# MrRoboto.net
KiCad netlist of a schematic drawn in EAGLE
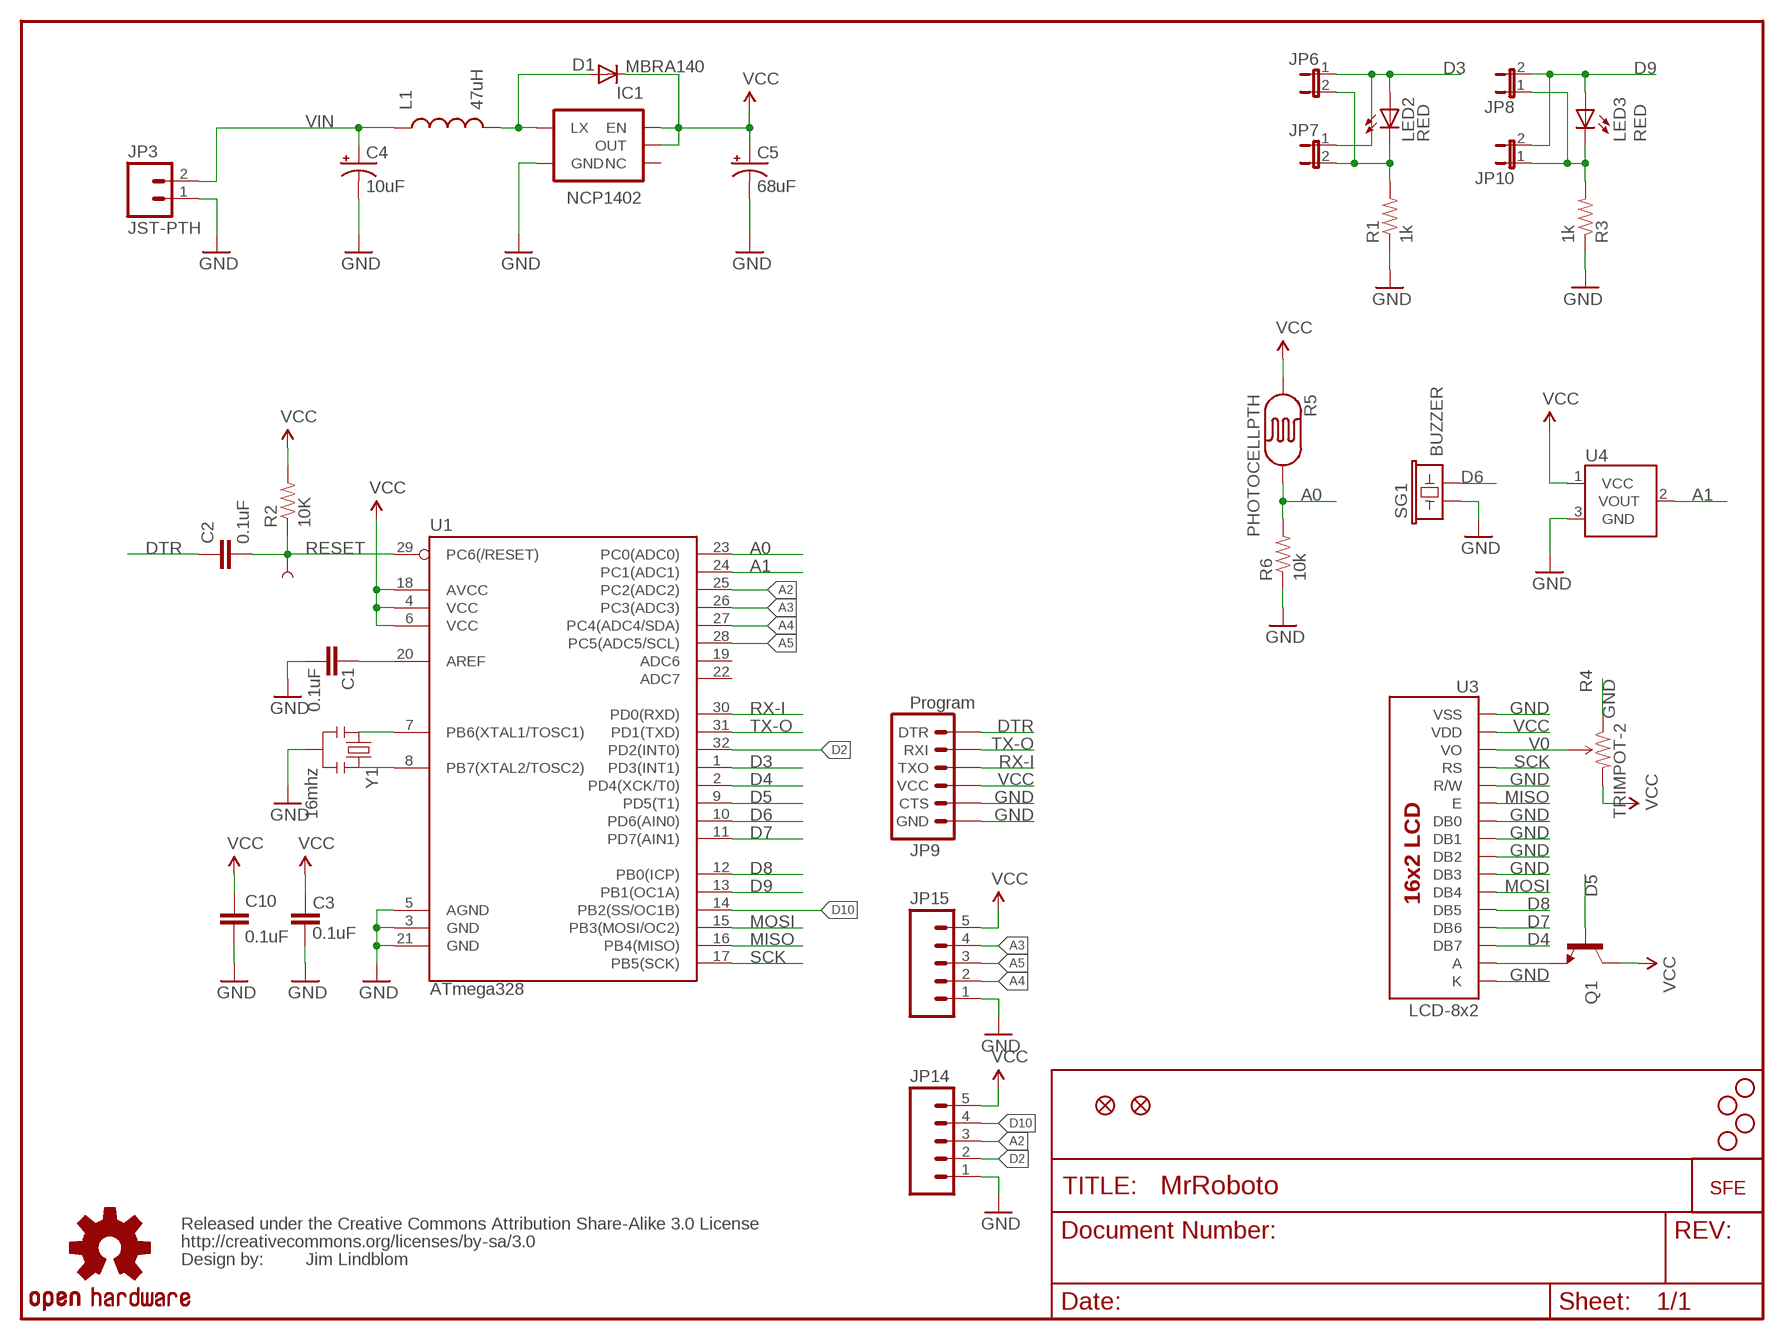
[diagram p0: schematic, sheet 1]

(export (version "E")
  (design (tool "Eeschema 10.0.6"))
  (components
    (comp (ref "C1")
      (value "0.1uF")
      (footprint "eagle-import:0402-CAP")
      (libsource (lib "eagle-import") (part "CAP0402-CAP"))
    )
    (comp (ref "C2")
      (value "0.1uF")
      (footprint "eagle-import:0402-CAP")
      (libsource (lib "eagle-import") (part "CAP0402-CAP"))
    )
    (comp (ref "C3")
      (value "0.1uF")
      (footprint "eagle-import:0402-CAP")
      (libsource (lib "eagle-import") (part "CAP0402-CAP"))
    )
    (comp (ref "C4")
      (value "10uF")
      (footprint "eagle-import:EIA3216")
      (libsource (lib "eagle-import") (part "CAP_POL1206"))
    )
    (comp (ref "C5")
      (value "68uF")
      (footprint "eagle-import:EIA3528")
      (libsource (lib "eagle-import") (part "CAP_POL3528"))
    )
    (comp (ref "C10")
      (value "0.1uF")
      (footprint "eagle-import:0402-CAP")
      (libsource (lib "eagle-import") (part "CAP0402-CAP"))
    )
    (comp (ref "D1")
      (value "MBRA140")
      (footprint "eagle-import:SMA-DIODE")
      (libsource (lib "eagle-import") (part "DIODESMA"))
    )
    (comp (ref "IC1")
      (value "NCP1402")
      (footprint "eagle-import:SOT23-5")
      (libsource (lib "eagle-import") (part "V_REG_NCP1400SOT23-5"))
    )
    (comp (ref "JP1")
      (value "Long, Plastic")
      (footprint "eagle-import:STAND-OFF")
      (libsource (lib "eagle-import") (part "STAND-OFF"))
    )
    (comp (ref "JP2")
      (value "Long, Plastic")
      (footprint "eagle-import:STAND-OFF")
      (libsource (lib "eagle-import") (part "STAND-OFF"))
    )
    (comp (ref "JP3")
      (value "JST-PTH")
      (footprint "eagle-import:JST-2-PTH-KIT")
      (libsource (lib "eagle-import") (part "M02JST-PTH-2-KIT"))
    )
    (comp (ref "JP4")
      (value "Long, Plastic")
      (footprint "eagle-import:STAND-OFF")
      (libsource (lib "eagle-import") (part "STAND-OFF"))
    )
    (comp (ref "JP5")
      (value "Long, Plastic")
      (footprint "eagle-import:STAND-OFF")
      (libsource (lib "eagle-import") (part "STAND-OFF"))
    )
    (comp (ref "JP6")
      (value "JUMPER-2SMD-NO-NS")
      (footprint "eagle-import:SJ_2S-NO-NS")
      (libsource (lib "eagle-import") (part "JUMPER-2SMD-NO-NS"))
    )
    (comp (ref "JP7")
      (value "JUMPER-2SMD-NO-NS")
      (footprint "eagle-import:SJ_2S-NO-NS")
      (libsource (lib "eagle-import") (part "JUMPER-2SMD-NO-NS"))
    )
    (comp (ref "JP8")
      (value "JUMPER-2SMD-NO-NS")
      (footprint "eagle-import:SJ_2S-NO-NS")
      (libsource (lib "eagle-import") (part "JUMPER-2SMD-NO-NS"))
    )
    (comp (ref "JP9")
      (value "Program")
      (footprint "eagle-import:1X06-KIT")
      (libsource (lib "eagle-import") (part "ARDUINO_SERIAL_PROGRAMPTH-KIT"))
    )
    (comp (ref "JP10")
      (value "JUMPER-2SMD-NO-NS")
      (footprint "eagle-import:SJ_2S-NO-NS")
      (libsource (lib "eagle-import") (part "JUMPER-2SMD-NO-NS"))
    )
    (comp (ref "JP11")
      (value "FIDUCIAL1X2.5")
      (footprint "eagle-import:FIDUCIAL-1X2.5")
      (libsource (lib "eagle-import") (part "FIDUCIAL1X2.5"))
    )
    (comp (ref "JP12")
      (value "FIDUCIAL1X2.5")
      (footprint "eagle-import:FIDUCIAL-1X2.5")
      (libsource (lib "eagle-import") (part "FIDUCIAL1X2.5"))
    )
    (comp (ref "JP14")
      (value "M05PTH")
      (footprint "eagle-import:1X05")
      (libsource (lib "eagle-import") (part "M05PTH"))
    )
    (comp (ref "JP15")
      (value "M05PTH")
      (footprint "eagle-import:1X05")
      (libsource (lib "eagle-import") (part "M05PTH"))
    )
    (comp (ref "L1")
      (value "47uH")
      (footprint "eagle-import:CR54")
      (libsource (lib "eagle-import") (part "INDUCTORCR54"))
    )
    (comp (ref "LED2")
      (value "RED")
      (footprint "eagle-import:LED5MM-KIT")
      (libsource (lib "eagle-import") (part "LED5MM-KIT"))
    )
    (comp (ref "LED3")
      (value "RED")
      (footprint "eagle-import:LED5MM-KIT")
      (libsource (lib "eagle-import") (part "LED5MM-KIT"))
    )
    (comp (ref "Q1")
      (value "TRANSISTOR_NPNSOT23")
      (footprint "eagle-import:SOT23")
      (libsource (lib "eagle-import") (part "TRANSISTOR_NPNSOT23"))
    )
    (comp (ref "R1")
      (value "1k")
      (footprint "eagle-import:AXIAL-0.3-KIT")
      (libsource (lib "eagle-import") (part "RESISTORKIT"))
    )
    (comp (ref "R2")
      (value "10K")
      (footprint "eagle-import:0402-RES")
      (libsource (lib "eagle-import") (part "RESISTOR0402-RES"))
    )
    (comp (ref "R3")
      (value "1k")
      (footprint "eagle-import:AXIAL-0.3-KIT")
      (libsource (lib "eagle-import") (part "RESISTORKIT"))
    )
    (comp (ref "R4")
      (value "TRIMPOT-2")
      (footprint "eagle-import:TRIMPOT_TC33")
      (libsource (lib "eagle-import") (part "TRIMPOT-2"))
    )
    (comp (ref "R5")
      (value "PHOTOCELLPTH")
      (footprint "eagle-import:PHOTOCELL-KIT")
      (libsource (lib "eagle-import") (part "PHOTOCELLPTH-KIT"))
    )
    (comp (ref "R6")
      (value "10k")
      (footprint "eagle-import:0402-RES")
      (libsource (lib "eagle-import") (part "RESISTOR0402-RES"))
    )
    (comp (ref "SG1")
      (value "BUZZER")
      (footprint "eagle-import:BUZZER-12MM-NS-KIT")
      (libsource (lib "eagle-import") (part "BUZZERPTH-NS-KIT"))
    )
    (comp (ref "TP1")
      (value "TP")
      (footprint "eagle-import:PAD.03X.05")
      (libsource (lib "eagle-import") (part "TEST-POINT3X5"))
    )
    (comp (ref "U$1")
      (value "CREATIVE_COMMONS")
      (footprint "eagle-import:CREATIVE_COMMONS")
      (libsource (lib "eagle-import") (part "CREATIVE_COMMONS"))
    )
    (comp (ref "U$2")
      (value "OSHW-LOGOM")
      (footprint "eagle-import:OSHW-LOGO-M")
      (libsource (lib "eagle-import") (part "OSHW-LOGOM"))
    )
    (comp (ref "U$3")
      (value "LOGO-SFENEW")
      (footprint "eagle-import:SFE-NEW-WEBLOGO")
      (libsource (lib "eagle-import") (part "LOGO-SFENEW"))
    )
    (comp (ref "U1")
      (value "ATmega328")
      (footprint "eagle-import:TQFP32-08")
      (libsource (lib "eagle-import") (part "ATMEGA168"))
    )
    (comp (ref "U3")
      (value "LCD-8x2")
      (footprint "eagle-import:LCD-8X2-KIT")
      (libsource (lib "eagle-import") (part "LCD-16X28X2-KIT"))
    )
    (comp (ref "U4")
      (value "TMP36TO-92-KIT")
      (footprint "eagle-import:TO-92-KIT")
      (libsource (lib "eagle-import") (part "TMP36TO-92-KIT"))
    )
    (comp (ref "Y1")
      (value "16mhz")
      (footprint "eagle-import:RESONATOR-SMD")
      (libsource (lib "eagle-import") (part "RESONATORSMD"))
    )
  )
  (nets
    (net (code "1") (name "/A0") (class "Default")
      (node (ref "R5") (pin "2") (pinfunction "P$2_2") (pintype "bidirectional"))
      (node (ref "R6") (pin "2") (pinfunction "2_2") (pintype "passive"))
      (node (ref "U1") (pin "23") (pinfunction "PC0(ADC0)_23") (pintype "bidirectional"))
    )
    (net (code "2") (name "/A1") (class "Default")
      (node (ref "U1") (pin "24") (pinfunction "PC1(ADC1)_24") (pintype "bidirectional"))
      (node (ref "U4") (pin "2") (pinfunction "VOUT_2") (pintype "bidirectional"))
    )
    (net (code "3") (name "/D3") (class "Default")
      (node (ref "JP6") (pin "1") (pinfunction "1_1") (pintype "passive"))
      (node (ref "JP7") (pin "1") (pinfunction "1_1") (pintype "passive"))
      (node (ref "LED2") (pin "A") (pinfunction "A_A") (pintype "passive"))
      (node (ref "U1") (pin "1") (pinfunction "PD3(INT1)_1") (pintype "bidirectional"))
    )
    (net (code "4") (name "/D4") (class "Default")
      (node (ref "U1") (pin "2") (pinfunction "PD4(XCK/T0)_2") (pintype "bidirectional"))
      (node (ref "U3") (pin "14") (pinfunction "DB7_14") (pintype "bidirectional"))
    )
    (net (code "5") (name "/D5") (class "Default")
      (node (ref "Q1") (pin "1") (pinfunction "B_1") (pintype "passive"))
      (node (ref "U1") (pin "9") (pinfunction "PD5(T1)_9") (pintype "bidirectional"))
    )
    (net (code "6") (name "/D6") (class "Default")
      (node (ref "SG1") (pin "-") (pinfunction "2_-") (pintype "passive"))
      (node (ref "U1") (pin "10") (pinfunction "PD6(AIN0)_10") (pintype "bidirectional"))
    )
    (net (code "7") (name "/D7") (class "Default")
      (node (ref "U1") (pin "11") (pinfunction "PD7(AIN1)_11") (pintype "bidirectional"))
      (node (ref "U3") (pin "13") (pinfunction "DB6_13") (pintype "bidirectional"))
    )
    (net (code "8") (name "/D8") (class "Default")
      (node (ref "U1") (pin "12") (pinfunction "PB0(ICP)_12") (pintype "bidirectional"))
      (node (ref "U3") (pin "12") (pinfunction "DB5_12") (pintype "bidirectional"))
    )
    (net (code "9") (name "/D9") (class "Default")
      (node (ref "JP10") (pin "2") (pinfunction "2_2") (pintype "passive"))
      (node (ref "JP8") (pin "2") (pinfunction "2_2") (pintype "passive"))
      (node (ref "LED3") (pin "A") (pinfunction "A_A") (pintype "passive"))
      (node (ref "U1") (pin "13") (pinfunction "PB1(OC1A)_13") (pintype "bidirectional"))
    )
    (net (code "10") (name "/DTR") (class "Default")
      (node (ref "C2") (pin "1") (pinfunction "1_1") (pintype "passive"))
      (node (ref "JP9") (pin "1") (pinfunction "DTR_1") (pintype "passive"))
    )
    (net (code "11") (name "/MISO") (class "Default")
      (node (ref "U1") (pin "16") (pinfunction "PB4(MISO)_16") (pintype "bidirectional"))
      (node (ref "U3") (pin "6") (pinfunction "E_6") (pintype "input"))
    )
    (net (code "12") (name "/MOSI") (class "Default")
      (node (ref "U1") (pin "15") (pinfunction "PB3(MOSI/OC2)_15") (pintype "bidirectional"))
      (node (ref "U3") (pin "11") (pinfunction "DB4_11") (pintype "bidirectional"))
    )
    (net (code "13") (name "/RESET") (class "Default")
      (node (ref "C2") (pin "2") (pinfunction "2_2") (pintype "passive"))
      (node (ref "R2") (pin "1") (pinfunction "1_1") (pintype "passive"))
      (node (ref "TP1") (pin "P$1") (pinfunction "1_P$1") (pintype "bidirectional"))
      (node (ref "U1") (pin "29") (pinfunction "PC6(/RESET)_29") (pintype "bidirectional"))
    )
    (net (code "14") (name "/RX-I") (class "Default")
      (node (ref "JP9") (pin "3") (pinfunction "TXO_3") (pintype "passive"))
      (node (ref "U1") (pin "30") (pinfunction "PD0(RXD)_30") (pintype "bidirectional"))
    )
    (net (code "15") (name "/SCK") (class "Default")
      (node (ref "U1") (pin "17") (pinfunction "PB5(SCK)_17") (pintype "bidirectional"))
      (node (ref "U3") (pin "4") (pinfunction "RS_4") (pintype "input"))
    )
    (net (code "16") (name "/TX-O") (class "Default")
      (node (ref "JP9") (pin "2") (pinfunction "RXI_2") (pintype "passive"))
      (node (ref "U1") (pin "31") (pinfunction "PD1(TXD)_31") (pintype "bidirectional"))
    )
    (net (code "17") (name "/V0") (class "Default")
      (node (ref "R4") (pin "2") (pinfunction "WIPER_2") (pintype "passive"))
      (node (ref "U3") (pin "3") (pinfunction "VO_3") (pintype "bidirectional"))
    )
    (net (code "18") (name "/VIN") (class "Default")
      (node (ref "C4") (pin "A") (pinfunction "+_A") (pintype "passive"))
      (node (ref "JP3") (pin "2") (pinfunction "2_2") (pintype "passive"))
      (node (ref "L1") (pin "P$1") (pinfunction "1_P$1") (pintype "passive"))
    )
    (net (code "19") (name "A2") (class "Default")
      (node (ref "JP14") (pin "3") (pinfunction "3_3") (pintype "passive"))
      (node (ref "U1") (pin "25") (pinfunction "PC2(ADC2)_25") (pintype "bidirectional"))
    )
    (net (code "20") (name "A3") (class "Default")
      (node (ref "JP15") (pin "4") (pinfunction "4_4") (pintype "passive"))
      (node (ref "U1") (pin "26") (pinfunction "PC3(ADC3)_26") (pintype "bidirectional"))
    )
    (net (code "21") (name "A4") (class "Default")
      (node (ref "JP15") (pin "2") (pinfunction "2_2") (pintype "passive"))
      (node (ref "U1") (pin "27") (pinfunction "PC4(ADC4/SDA)_27") (pintype "bidirectional"))
    )
    (net (code "22") (name "A5") (class "Default")
      (node (ref "JP15") (pin "3") (pinfunction "3_3") (pintype "passive"))
      (node (ref "U1") (pin "28") (pinfunction "PC5(ADC5/SCL)_28") (pintype "bidirectional"))
    )
    (net (code "23") (name "D2") (class "Default")
      (node (ref "JP14") (pin "2") (pinfunction "2_2") (pintype "passive"))
      (node (ref "U1") (pin "32") (pinfunction "PD2(INT0)_32") (pintype "bidirectional"))
    )
    (net (code "24") (name "D10") (class "Default")
      (node (ref "JP14") (pin "4") (pinfunction "4_4") (pintype "passive"))
      (node (ref "U1") (pin "14") (pinfunction "PB2(SS/OC1B)_14") (pintype "bidirectional"))
    )
    (net (code "25") (name "GND") (class "Default")
      (node (ref "C1") (pin "1") (pinfunction "1_1") (pintype "passive"))
      (node (ref "C10") (pin "2") (pinfunction "2_2") (pintype "passive"))
      (node (ref "C3") (pin "1") (pinfunction "1_1") (pintype "passive"))
      (node (ref "C4") (pin "C") (pinfunction "-_C") (pintype "passive"))
      (node (ref "C5") (pin "C") (pinfunction "-_C") (pintype "passive"))
      (node (ref "IC1") (pin "4") (pinfunction "GND_4") (pintype "input"))
      (node (ref "JP14") (pin "1") (pinfunction "1_1") (pintype "passive"))
      (node (ref "JP15") (pin "1") (pinfunction "1_1") (pintype "passive"))
      (node (ref "JP3") (pin "1") (pinfunction "1_1") (pintype "passive"))
      (node (ref "JP9") (pin "5") (pinfunction "CTS_5") (pintype "passive"))
      (node (ref "JP9") (pin "6") (pinfunction "GND_6") (pintype "passive"))
      (node (ref "R1") (pin "P$1") (pinfunction "1_P$1") (pintype "passive"))
      (node (ref "R3") (pin "P$1") (pinfunction "1_P$1") (pintype "passive"))
      (node (ref "R4") (pin "1") (pinfunction "CCW_1") (pintype "passive"))
      (node (ref "R6") (pin "1") (pinfunction "1_1") (pintype "passive"))
      (node (ref "SG1") (pin "+") (pinfunction "1_+") (pintype "passive"))
      (node (ref "U1") (pin "21") (pinfunction "GND_21") (pintype "bidirectional"))
      (node (ref "U1") (pin "3") (pinfunction "GND_3") (pintype "bidirectional"))
      (node (ref "U1") (pin "5") (pinfunction "AGND_5") (pintype "bidirectional"))
      (node (ref "U3") (pin "1") (pinfunction "VSS_1") (pintype "power_in"))
      (node (ref "U3") (pin "10") (pinfunction "DB3_10") (pintype "bidirectional"))
      (node (ref "U3") (pin "16") (pinfunction "K_16") (pintype "power_in"))
      (node (ref "U3") (pin "5") (pinfunction "R/W_5") (pintype "input"))
      (node (ref "U3") (pin "7") (pinfunction "DB0_7") (pintype "bidirectional"))
      (node (ref "U3") (pin "8") (pinfunction "DB1_8") (pintype "bidirectional"))
      (node (ref "U3") (pin "9") (pinfunction "DB2_9") (pintype "bidirectional"))
      (node (ref "U4") (pin "3") (pinfunction "GND_3") (pintype "bidirectional"))
      (node (ref "Y1") (pin "2") (pinfunction "2_2") (pintype "passive"))
    )
    (net (code "26") (name "Net-(IC1-LX)") (class "Default")
      (node (ref "D1") (pin "A") (pinfunction "A_A") (pintype "passive"))
      (node (ref "IC1") (pin "5") (pinfunction "LX_5") (pintype "input"))
      (node (ref "L1") (pin "P$2") (pinfunction "2_P$2") (pintype "passive"))
    )
    (net (code "27") (name "Net-(LED2-C)") (class "Default")
      (node (ref "JP6") (pin "2") (pinfunction "2_2") (pintype "passive"))
      (node (ref "JP7") (pin "2") (pinfunction "2_2") (pintype "passive"))
      (node (ref "LED2") (pin "K") (pinfunction "C_K") (pintype "passive"))
      (node (ref "R1") (pin "P$2") (pinfunction "2_P$2") (pintype "passive"))
    )
    (net (code "28") (name "Net-(LED3-C)") (class "Default")
      (node (ref "JP10") (pin "1") (pinfunction "1_1") (pintype "passive"))
      (node (ref "JP8") (pin "1") (pinfunction "1_1") (pintype "passive"))
      (node (ref "LED3") (pin "K") (pinfunction "C_K") (pintype "passive"))
      (node (ref "R3") (pin "P$2") (pinfunction "2_P$2") (pintype "passive"))
    )
    (net (code "29") (name "Net-(Q1-E)") (class "Default")
      (node (ref "Q1") (pin "2") (pinfunction "E_2") (pintype "passive"))
      (node (ref "U3") (pin "15") (pinfunction "A_15") (pintype "power_in"))
    )
    (net (code "30") (name "Net-(U1-AREF)") (class "Default")
      (node (ref "C1") (pin "2") (pinfunction "2_2") (pintype "passive"))
      (node (ref "U1") (pin "20") (pinfunction "AREF_20") (pintype "bidirectional"))
    )
    (net (code "31") (name "Net-(U1-PB6(XTAL1{slash}TOSC1))") (class "Default")
      (node (ref "U1") (pin "7") (pinfunction "PB6(XTAL1/TOSC1)_7") (pintype "bidirectional"))
      (node (ref "Y1") (pin "1") (pinfunction "1_1") (pintype "passive"))
    )
    (net (code "32") (name "Net-(U1-PB7(XTAL2{slash}TOSC2))") (class "Default")
      (node (ref "U1") (pin "8") (pinfunction "PB7(XTAL2/TOSC2)_8") (pintype "bidirectional"))
      (node (ref "Y1") (pin "3") (pinfunction "3_3") (pintype "passive"))
    )
    (net (code "33") (name "VCC") (class "Default")
      (node (ref "C10") (pin "1") (pinfunction "1_1") (pintype "passive"))
      (node (ref "C3") (pin "2") (pinfunction "2_2") (pintype "passive"))
      (node (ref "C5") (pin "A") (pinfunction "+_A") (pintype "passive"))
      (node (ref "D1") (pin "C") (pinfunction "C_C") (pintype "passive"))
      (node (ref "IC1") (pin "1") (pinfunction "EN_1") (pintype "input"))
      (node (ref "IC1") (pin "2") (pinfunction "OUT_2") (pintype "passive"))
      (node (ref "JP14") (pin "5") (pinfunction "5_5") (pintype "passive"))
      (node (ref "JP15") (pin "5") (pinfunction "5_5") (pintype "passive"))
      (node (ref "JP9") (pin "4") (pinfunction "VCC_4") (pintype "passive"))
      (node (ref "Q1") (pin "3") (pinfunction "C_3") (pintype "passive"))
      (node (ref "R2") (pin "2") (pinfunction "2_2") (pintype "passive"))
      (node (ref "R4") (pin "3") (pinfunction "CW_3") (pintype "passive"))
      (node (ref "R5") (pin "1") (pinfunction "P$1_1") (pintype "bidirectional"))
      (node (ref "U1") (pin "18") (pinfunction "AVCC_18") (pintype "bidirectional"))
      (node (ref "U1") (pin "4") (pinfunction "VCC_4") (pintype "bidirectional"))
      (node (ref "U1") (pin "6") (pinfunction "VCC_6") (pintype "bidirectional"))
      (node (ref "U3") (pin "2") (pinfunction "VDD_2") (pintype "power_in"))
      (node (ref "U4") (pin "1") (pinfunction "VCC_1") (pintype "bidirectional"))
    )
    (net (code "34") (name "unconnected-(IC1-NC-Pad3)") (class "Default")
      (node (ref "IC1") (pin "3") (pinfunction "NC_3") (pintype "input"))
    )
    (net (code "35") (name "unconnected-(U1-ADC6-Pad19)") (class "Default")
      (node (ref "U1") (pin "19") (pinfunction "ADC6_19") (pintype "bidirectional"))
    )
    (net (code "36") (name "unconnected-(U1-ADC7-Pad22)") (class "Default")
      (node (ref "U1") (pin "22") (pinfunction "ADC7_22") (pintype "bidirectional"))
    )
  )
)
